# Clocks.net
KiCad netlist of a schematic drawn in Altium Designer
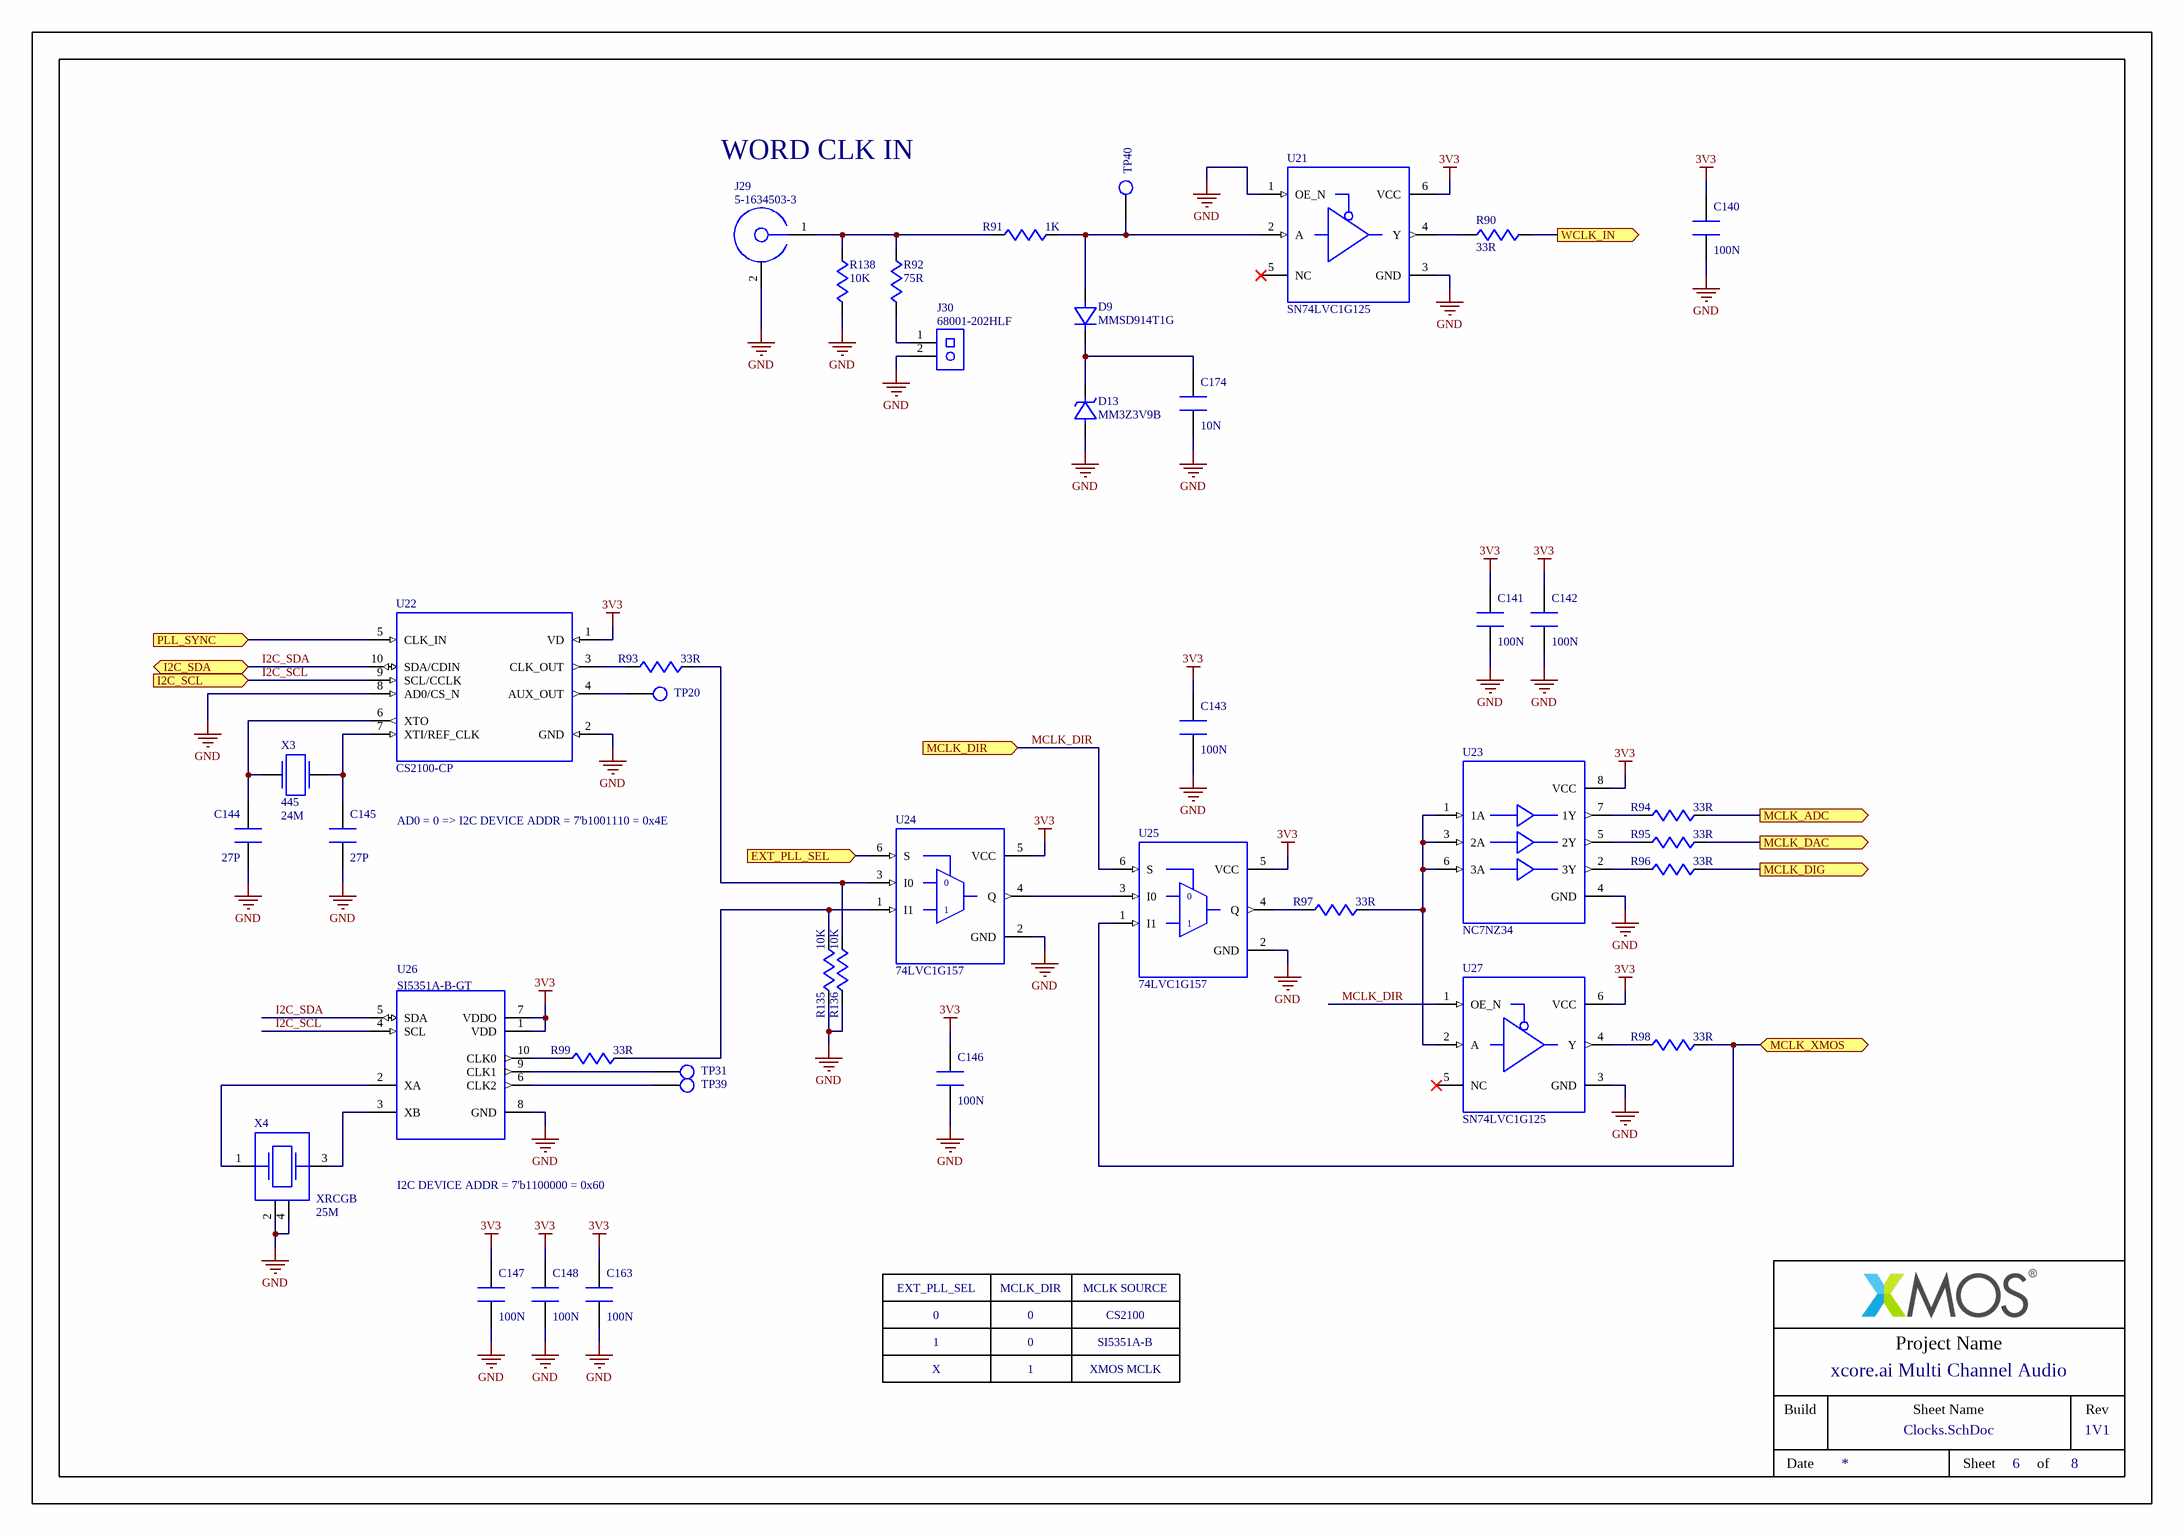
[diagram p0: Clocks.SchDoc]

(export (version "E")
  (design (tool "Eeschema 10.0.6"))
  (components
    (comp (ref "C140")
      (value "100N")
      (footprint "CAPC1005X55N")
      (description "CHIP CAPACITOR, CERAMIC, 100NF, 16V, 10%, X7R, 0402")
      (fields (field (name "PART NUMBER") "STD-06-0048") (field (name "TOLERANCE") "10%"))
      (libsource (lib "JG_StandardLibrary") (part "CAP_NP"))
    )
    (comp (ref "C141")
      (value "100N")
      (footprint "CAPC1005X55N")
      (description "CHIP CAPACITOR, CERAMIC, 100NF, 16V, 10%, X7R, 0402")
      (fields (field (name "PART NUMBER") "STD-06-0048") (field (name "TOLERANCE") "10%"))
      (libsource (lib "JG_StandardLibrary") (part "CAP_NP"))
    )
    (comp (ref "C142")
      (value "100N")
      (footprint "CAPC1005X55N")
      (description "CHIP CAPACITOR, CERAMIC, 100NF, 16V, 10%, X7R, 0402")
      (fields (field (name "PART NUMBER") "STD-06-0048") (field (name "TOLERANCE") "10%"))
      (libsource (lib "JG_StandardLibrary") (part "CAP_NP"))
    )
    (comp (ref "C143")
      (value "100N")
      (footprint "CAPC1005X55N")
      (description "CHIP CAPACITOR, CERAMIC, 100NF, 16V, 10%, X7R, 0402")
      (fields (field (name "PART NUMBER") "STD-06-0048") (field (name "TOLERANCE") "10%"))
      (libsource (lib "JG_StandardLibrary") (part "CAP_NP"))
    )
    (comp (ref "C144")
      (value "27P")
      (footprint "CAPC1005X55N")
      (description "CHIP CAPACITOR, CERAMIC, 27PF, 50V, 5%, NP0, 0402")
      (fields (field (name "PART NUMBER") "STD-06-0018") (field (name "TOLERANCE") "5%"))
      (libsource (lib "JG_StandardLibrary") (part "CAP_NP"))
    )
    (comp (ref "C145")
      (value "27P")
      (footprint "CAPC1005X55N")
      (description "CHIP CAPACITOR, CERAMIC, 27PF, 50V, 5%, NP0, 0402")
      (fields (field (name "PART NUMBER") "STD-06-0018") (field (name "TOLERANCE") "5%"))
      (libsource (lib "JG_StandardLibrary") (part "CAP_NP"))
    )
    (comp (ref "C146")
      (value "100N")
      (footprint "CAPC1005X55N")
      (description "CHIP CAPACITOR, CERAMIC, 100NF, 16V, 10%, X7R, 0402")
      (fields (field (name "PART NUMBER") "STD-06-0048") (field (name "TOLERANCE") "10%"))
      (libsource (lib "JG_StandardLibrary") (part "CAP_NP"))
    )
    (comp (ref "C147")
      (value "100N")
      (footprint "CAPC1005X55N")
      (description "CHIP CAPACITOR, CERAMIC, 100NF, 16V, 10%, X7R, 0402")
      (fields (field (name "PART NUMBER") "STD-06-0048") (field (name "TOLERANCE") "10%"))
      (libsource (lib "JG_StandardLibrary") (part "CAP_NP"))
    )
    (comp (ref "C148")
      (value "100N")
      (footprint "CAPC1005X55N")
      (description "CHIP CAPACITOR, CERAMIC, 100NF, 16V, 10%, X7R, 0402")
      (fields (field (name "PART NUMBER") "STD-06-0048") (field (name "TOLERANCE") "10%"))
      (libsource (lib "JG_StandardLibrary") (part "CAP_NP"))
    )
    (comp (ref "C163")
      (value "100N")
      (footprint "CAPC1005X55N")
      (description "CHIP CAPACITOR, CERAMIC, 100NF, 16V, 10%, X7R, 0402")
      (fields (field (name "PART NUMBER") "STD-06-0048") (field (name "TOLERANCE") "10%"))
      (libsource (lib "JG_StandardLibrary") (part "CAP_NP"))
    )
    (comp (ref "C174")
      (value "10N")
      (footprint "CAPC1005X55N")
      (description "CHIP CAPACITOR, CERAMIC, 10NF, 50V, 10%, X7R, 0402")
      (fields (field (name "PART NUMBER") "STD-06-0042") (field (name "TOLERANCE") "10%"))
      (libsource (lib "JG_StandardLibrary") (part "CAP_NP"))
    )
    (comp (ref "D9")
      (value "MMSD914T1G")
      (footprint "SOD3716X135N")
      (description "Diode, 100V, 0.2A, SOD123")
      (fields (field (name "PART NUMBER") "GEN-16-0055") (field (name "MANUFACTURER") "ON Semiconductor"))
      (libsource (lib "JG_GeneralLibrary") (part "DIODE"))
    )
    (comp (ref "D13")
      (value "MM3Z3V9B")
      (footprint "SODFL2513X100N")
      (description "Zener Diode, 3.9V, 2%, 0.2W, SOD-323F")
      (fields (field (name "PART NUMBER") "GEN-16-0053") (field (name "MANUFACTURER") "ON Semiconductor"))
      (libsource (lib "JG_GeneralLibrary") (part "ZENER"))
    )
    (comp (ref "J29")
      (value "5-1634503-3")
      (footprint "CON_TE_5_1634503")
      (description "BNC Jack, Board Mount, Vertical, 75 ohm, w/Mounting Posts")
      (fields (field (name "PART NUMBER") "GEN-01-0127") (field (name "MANUFACTURER") "TE Connectivity"))
      (libsource (lib "JG_GeneralLibrary") (part "COAX_2_A"))
    )
    (comp (ref "J30")
      (value "68001-202HLF")
      (footprint "HDR_FCI_68001_202")
      (description "Pin Header, Male, Vertical, Through Hole, 2 Way, 1x2, 0.1 Inch Pitch")
      (fields (field (name "PART NUMBER") "GEN-01-0011") (field (name "MANUFACTURER") "FCI"))
      (libsource (lib "JG_GeneralLibrary") (part "PIN_HEADER_1X2"))
    )
    (comp (ref "R90")
      (value "33R")
      (footprint "RESC1608X55N")
      (description "CHIP RESISTOR, 33 OHM, 0.1W, 1%, 0603")
      (fields (field (name "PART NUMBER") "STD-02-0026") (field (name "TOLERANCE") "1%"))
      (libsource (lib "JG_StandardLibrary") (part "RES"))
    )
    (comp (ref "R91")
      (value "1K")
      (footprint "RESC1608X55N")
      (description "CHIP RESISTOR, 1.0K OHM, 0.1W, 1%, 0603")
      (fields (field (name "PART NUMBER") "STD-02-0062") (field (name "TOLERANCE") "1%"))
      (libsource (lib "JG_StandardLibrary") (part "RES"))
    )
    (comp (ref "R92")
      (value "75R")
      (footprint "RESC3116X65N")
      (description "CHIP RESISTOR, 75 OHM, 0.25W, 1%, 1206")
      (fields (field (name "PART NUMBER") "STD-05-0035") (field (name "TOLERANCE") "1%"))
      (libsource (lib "JG_StandardLibrary") (part "RES"))
    )
    (comp (ref "R93")
      (value "33R")
      (footprint "RESC1608X55N")
      (description "CHIP RESISTOR, 33 OHM, 0.1W, 1%, 0603")
      (fields (field (name "PART NUMBER") "STD-02-0026") (field (name "TOLERANCE") "1%"))
      (libsource (lib "JG_StandardLibrary") (part "RES"))
    )
    (comp (ref "R94")
      (value "33R")
      (footprint "RESC1608X55N")
      (description "CHIP RESISTOR, 33 OHM, 0.1W, 1%, 0603")
      (fields (field (name "PART NUMBER") "STD-02-0026") (field (name "TOLERANCE") "1%"))
      (libsource (lib "JG_StandardLibrary") (part "RES"))
    )
    (comp (ref "R95")
      (value "33R")
      (footprint "RESC1608X55N")
      (description "CHIP RESISTOR, 33 OHM, 0.1W, 1%, 0603")
      (fields (field (name "PART NUMBER") "STD-02-0026") (field (name "TOLERANCE") "1%"))
      (libsource (lib "JG_StandardLibrary") (part "RES"))
    )
    (comp (ref "R96")
      (value "33R")
      (footprint "RESC1608X55N")
      (description "CHIP RESISTOR, 33 OHM, 0.1W, 1%, 0603")
      (fields (field (name "PART NUMBER") "STD-02-0026") (field (name "TOLERANCE") "1%"))
      (libsource (lib "JG_StandardLibrary") (part "RES"))
    )
    (comp (ref "R97")
      (value "33R")
      (footprint "RESC1608X55N")
      (description "CHIP RESISTOR, 33 OHM, 0.1W, 1%, 0603")
      (fields (field (name "PART NUMBER") "STD-02-0026") (field (name "TOLERANCE") "1%"))
      (libsource (lib "JG_StandardLibrary") (part "RES"))
    )
    (comp (ref "R98")
      (value "33R")
      (footprint "RESC1608X55N")
      (description "CHIP RESISTOR, 33 OHM, 0.1W, 1%, 0603")
      (fields (field (name "PART NUMBER") "STD-02-0026") (field (name "TOLERANCE") "1%"))
      (libsource (lib "JG_StandardLibrary") (part "RES"))
    )
    (comp (ref "R99")
      (value "33R")
      (footprint "RESC1608X55N")
      (description "CHIP RESISTOR, 33 OHM, 0.1W, 1%, 0603")
      (fields (field (name "PART NUMBER") "STD-02-0026") (field (name "TOLERANCE") "1%"))
      (libsource (lib "JG_StandardLibrary") (part "RES"))
    )
    (comp (ref "R135")
      (value "10K")
      (footprint "RESC1608X55N")
      (description "CHIP RESISTOR, 10K OHM, 0.1W, 1%, 0603")
      (fields (field (name "PART NUMBER") "STD-02-0086") (field (name "TOLERANCE") "1%"))
      (libsource (lib "JG_StandardLibrary") (part "RES"))
    )
    (comp (ref "R136")
      (value "10K")
      (footprint "RESC1608X55N")
      (description "CHIP RESISTOR, 10K OHM, 0.1W, 1%, 0603")
      (fields (field (name "PART NUMBER") "STD-02-0086") (field (name "TOLERANCE") "1%"))
      (libsource (lib "JG_StandardLibrary") (part "RES"))
    )
    (comp (ref "R138")
      (value "10K")
      (footprint "RESC1608X55N")
      (description "CHIP RESISTOR, 10K OHM, 0.1W, 1%, 0603")
      (fields (field (name "PART NUMBER") "STD-02-0086") (field (name "TOLERANCE") "1%"))
      (libsource (lib "JG_StandardLibrary") (part "RES"))
    )
    (comp (ref "TP20")
      (value "TESTPOINT")
      (footprint "TESTPOINT_THRU")
      (description "Testpoint, Through Hole")
      (fields (field (name "PART NUMBER") "GEN-24-0002") (field (name "MANUFACTURER") "NA"))
      (libsource (lib "JG_GeneralLibrary") (part "TESTPOINT"))
    )
    (comp (ref "TP31")
      (value "TESTPOINT")
      (footprint "TESTPOINT_THRU")
      (description "Testpoint, Through Hole")
      (fields (field (name "PART NUMBER") "GEN-24-0002") (field (name "MANUFACTURER") "NA"))
      (libsource (lib "JG_GeneralLibrary") (part "TESTPOINT"))
    )
    (comp (ref "TP39")
      (value "TESTPOINT")
      (footprint "TESTPOINT_THRU")
      (description "Testpoint, Through Hole")
      (fields (field (name "PART NUMBER") "GEN-24-0002") (field (name "MANUFACTURER") "NA"))
      (libsource (lib "JG_GeneralLibrary") (part "TESTPOINT"))
    )
    (comp (ref "TP40")
      (value "TESTPOINT")
      (footprint "TESTPOINT_SMD_1MM")
      (description "Testpoint, SMD, 1mm")
      (fields (field (name "PART NUMBER") "GEN-24-0003") (field (name "MANUFACTURER") "NA"))
      (libsource (lib "JG_GeneralLibrary") (part "TESTPOINT"))
    )
    (comp (ref "U21")
      (value "SN74LVC1G125")
      (footprint "TI_R_PUSON_N6")
      (description "Single Buffer with 3-State Output, LVC Series, SON6")
      (fields (field (name "PART NUMBER") "GEN-11-0049") (field (name "MANUFACTURER") "Texas Instruments"))
      (libsource (lib "JG_GeneralLibrary") (part "SINGLEGATE_125_B"))
    )
    (comp (ref "U22")
      (value "CS2100-CP")
      (footprint "SOP50P490X110-10N")
      (description "Fractional-N Clock Multiplier, I2C/SPI Control, MSOP10")
      (fields (field (name "PART NUMBER") "GEN-07-0007") (field (name "MANUFACTURER") "Cirrus Logic"))
      (libsource (lib "JG_GeneralLibrary") (part "CIRRUS_CS2100_CP"))
    )
    (comp (ref "U23")
      (value "NC7NZ34")
      (footprint "SOP50P310X100-8N")
      (description "Triple Logic Buffer, UHS Series, US8")
      (fields (field (name "PART NUMBER") "GEN-11-0025") (field (name "MANUFACTURER") "Fairchild"))
      (libsource (lib "JG_GeneralLibrary") (part "TRIPLEGATE_34_A"))
    )
    (comp (ref "U24")
      (value "74LVC1G157")
      (footprint "SOT95P280X145-6N")
      (description "Two Input Non-Inverting Multiplexer, LVC Series, TSOP6")
      (fields (field (name "PART NUMBER") "GEN-11-0050") (field (name "MANUFACTURER") "Nexperia"))
      (libsource (lib "JG_GeneralLibrary") (part "SINGLEGATE_157_A"))
    )
    (comp (ref "U25")
      (value "74LVC1G157")
      (footprint "SOT95P280X145-6N")
      (description "Two Input Non-Inverting Multiplexer, LVC Series, TSOP6")
      (fields (field (name "PART NUMBER") "GEN-11-0050") (field (name "MANUFACTURER") "Nexperia"))
      (libsource (lib "JG_GeneralLibrary") (part "SINGLEGATE_157_A"))
    )
    (comp (ref "U26")
      (value "SI5351A-B-GT")
      (footprint "SOP50P490X110-10N")
      (description "Clock Generator, I2C Programmable, XTAL Input, 3 Outputs, MSOP10")
      (fields (field (name "PART NUMBER") "GEN-07-0005") (field (name "MANUFACTURER") "Silicon Labs"))
      (libsource (lib "JG_GeneralLibrary") (part "SI_LABS_SI5351A_MSOP"))
    )
    (comp (ref "U27")
      (value "SN74LVC1G125")
      (footprint "TI_R_PUSON_N6")
      (description "Single Buffer with 3-State Output, LVC Series, SON6")
      (fields (field (name "PART NUMBER") "GEN-11-0049") (field (name "MANUFACTURER") "Texas Instruments"))
      (libsource (lib "JG_GeneralLibrary") (part "SINGLEGATE_125_B"))
    )
    (comp (ref "X3")
      (value "445")
      (footprint "XTAL_CTS_445")
      (description "Crystal, 24MHz, Freq Tol. ±30ppm, Freq Stab. ±30ppm, CL 18pF, Max ESR 40 Ohm, 5x3.2mm SMD")
      (fields
        (field (name "FREQUENCY") "24M")
        (field (name "PART NUMBER") "GEN-15-0041")
        (field (name "MANUFACTURER") "CTS")
      )
      (libsource (lib "JG_GeneralLibrary") (part "CRYSTAL"))
    )
    (comp (ref "X4")
      (value "XRCGB")
      (footprint "OSCCC200X160X70N")
      (description "Crystal, 25MHz, Freq Tol. ±25ppm, Freq Stab. ±40ppm, CL 8pF, Max ESR 80 Ohm, 2.0x1.6mm SMD")
      (fields
        (field (name "FREQUENCY") "25M")
        (field (name "PART NUMBER") "GEN-15-0039")
        (field (name "MANUFACTURER") "Murata")
      )
      (libsource (lib "JG_GeneralLibrary") (part "CRYSTAL_4PIN_A"))
    )
  )
  (nets
    (net (code "1") (name "/EXT_PLL_SEL") (class "Default")
      (node (ref "U24") (pin "6") (pinfunction "S_6") (pintype "input"))
    )
    (net (code "2") (name "/I2C_SCL") (class "Default")
      (node (ref "U22") (pin "9") (pinfunction "SCL/CCLK_9") (pintype "input"))
      (node (ref "U26") (pin "4") (pinfunction "SCL_4") (pintype "input"))
    )
    (net (code "3") (name "/I2C_SDA") (class "Default")
      (node (ref "U22") (pin "10") (pinfunction "SDA/CDIN_10") (pintype "bidirectional"))
      (node (ref "U26") (pin "5") (pinfunction "SDA_5") (pintype "bidirectional"))
    )
    (net (code "4") (name "/MCLK_ADC") (class "Default")
      (node (ref "R94") (pin "2") (pinfunction "2_2") (pintype "passive"))
    )
    (net (code "5") (name "/MCLK_DAC") (class "Default")
      (node (ref "R95") (pin "2") (pinfunction "2_2") (pintype "passive"))
    )
    (net (code "6") (name "/MCLK_DIG") (class "Default")
      (node (ref "R96") (pin "2") (pinfunction "2_2") (pintype "passive"))
    )
    (net (code "7") (name "/MCLK_DIR") (class "Default")
      (node (ref "U25") (pin "6") (pinfunction "S_6") (pintype "input"))
      (node (ref "U27") (pin "1") (pinfunction "OE_N_1") (pintype "input"))
    )
    (net (code "8") (name "/MCLK_XMOS") (class "Default")
      (node (ref "R98") (pin "2") (pinfunction "2_2") (pintype "passive"))
      (node (ref "U25") (pin "1") (pinfunction "I1_1") (pintype "input"))
    )
    (net (code "9") (name "/PLL_SYNC") (class "Default")
      (node (ref "U22") (pin "5") (pinfunction "CLK_IN_5") (pintype "input"))
    )
    (net (code "10") (name "/WCLK_IN") (class "Default")
      (node (ref "R90") (pin "2") (pinfunction "2_2") (pintype "passive"))
    )
    (net (code "11") (name "3V3") (class "Default")
      (node (ref "C140") (pin "1") (pinfunction "1_1") (pintype "passive"))
      (node (ref "C141") (pin "1") (pinfunction "1_1") (pintype "passive"))
      (node (ref "C142") (pin "1") (pinfunction "1_1") (pintype "passive"))
      (node (ref "C143") (pin "1") (pinfunction "1_1") (pintype "passive"))
      (node (ref "C146") (pin "1") (pinfunction "1_1") (pintype "passive"))
      (node (ref "C147") (pin "1") (pinfunction "1_1") (pintype "passive"))
      (node (ref "C148") (pin "1") (pinfunction "1_1") (pintype "passive"))
      (node (ref "C163") (pin "1") (pinfunction "1_1") (pintype "passive"))
      (node (ref "U21") (pin "6") (pinfunction "VCC_6") (pintype "power_in"))
      (node (ref "U22") (pin "1") (pinfunction "VD_1") (pintype "input"))
      (node (ref "U23") (pin "8") (pinfunction "VCC_8") (pintype "power_in"))
      (node (ref "U24") (pin "5") (pinfunction "VCC_5") (pintype "power_in"))
      (node (ref "U25") (pin "5") (pinfunction "VCC_5") (pintype "power_in"))
      (node (ref "U26") (pin "1") (pinfunction "VDD_1") (pintype "power_in"))
      (node (ref "U26") (pin "7") (pinfunction "VDDO_7") (pintype "power_in"))
      (node (ref "U27") (pin "6") (pinfunction "VCC_6") (pintype "power_in"))
    )
    (net (code "12") (name "GND") (class "Default")
      (node (ref "C140") (pin "2") (pinfunction "2_2") (pintype "passive"))
      (node (ref "C141") (pin "2") (pinfunction "2_2") (pintype "passive"))
      (node (ref "C142") (pin "2") (pinfunction "2_2") (pintype "passive"))
      (node (ref "C143") (pin "2") (pinfunction "2_2") (pintype "passive"))
      (node (ref "C144") (pin "2") (pinfunction "2_2") (pintype "passive"))
      (node (ref "C145") (pin "2") (pinfunction "2_2") (pintype "passive"))
      (node (ref "C146") (pin "2") (pinfunction "2_2") (pintype "passive"))
      (node (ref "C147") (pin "2") (pinfunction "2_2") (pintype "passive"))
      (node (ref "C148") (pin "2") (pinfunction "2_2") (pintype "passive"))
      (node (ref "C163") (pin "2") (pinfunction "2_2") (pintype "passive"))
      (node (ref "C174") (pin "2") (pinfunction "2_2") (pintype "passive"))
      (node (ref "D13") (pin "2") (pinfunction "A_2") (pintype "passive"))
      (node (ref "J29") (pin "2") (pinfunction "2_2") (pintype "passive"))
      (node (ref "J30") (pin "2") (pinfunction "2_2") (pintype "passive"))
      (node (ref "R135") (pin "1") (pinfunction "1_1") (pintype "passive"))
      (node (ref "R136") (pin "1") (pinfunction "1_1") (pintype "passive"))
      (node (ref "R138") (pin "1") (pinfunction "1_1") (pintype "passive"))
      (node (ref "U21") (pin "1") (pinfunction "OE_N_1") (pintype "input"))
      (node (ref "U21") (pin "3") (pinfunction "GND_3") (pintype "power_in"))
      (node (ref "U22") (pin "2") (pinfunction "GND_2") (pintype "input"))
      (node (ref "U22") (pin "8") (pinfunction "AD0/CS_N_8") (pintype "input"))
      (node (ref "U23") (pin "4") (pinfunction "GND_4") (pintype "power_in"))
      (node (ref "U24") (pin "2") (pinfunction "GND_2") (pintype "power_in"))
      (node (ref "U25") (pin "2") (pinfunction "GND_2") (pintype "power_in"))
      (node (ref "U26") (pin "8") (pinfunction "GND_8") (pintype "power_in"))
      (node (ref "U27") (pin "3") (pinfunction "GND_3") (pintype "power_in"))
      (node (ref "X4") (pin "2") (pinfunction "CASE_2_2") (pintype "passive"))
      (node (ref "X4") (pin "4") (pinfunction "CASE_4_4") (pintype "passive"))
    )
    (net (code "13") (name "Net-(D9-A)") (class "Default")
      (node (ref "D9") (pin "2") (pinfunction "A_2") (pintype "passive"))
      (node (ref "R91") (pin "2") (pinfunction "2_2") (pintype "passive"))
      (node (ref "TP40") (pin "1") (pinfunction "1_1") (pintype "passive"))
      (node (ref "U21") (pin "2") (pinfunction "A_2") (pintype "input"))
    )
    (net (code "14") (name "Net-(D13-K)") (class "Default")
      (node (ref "C174") (pin "1") (pinfunction "1_1") (pintype "passive"))
      (node (ref "D13") (pin "1") (pinfunction "K_1") (pintype "passive"))
      (node (ref "D9") (pin "1") (pinfunction "K_1") (pintype "passive"))
    )
    (net (code "15") (name "Net-(J29-Pad1)") (class "Default")
      (node (ref "J29") (pin "1") (pinfunction "1_1") (pintype "passive"))
      (node (ref "R138") (pin "2") (pinfunction "2_2") (pintype "passive"))
      (node (ref "R91") (pin "1") (pinfunction "1_1") (pintype "passive"))
      (node (ref "R92") (pin "2") (pinfunction "2_2") (pintype "passive"))
    )
    (net (code "16") (name "Net-(J30-Pad1)") (class "Default")
      (node (ref "J30") (pin "1") (pinfunction "1_1") (pintype "passive"))
      (node (ref "R92") (pin "1") (pinfunction "1_1") (pintype "passive"))
    )
    (net (code "17") (name "Net-(U21-Y)") (class "Default")
      (node (ref "R90") (pin "1") (pinfunction "1_1") (pintype "passive"))
      (node (ref "U21") (pin "4") (pinfunction "Y_4") (pintype "output"))
    )
    (net (code "18") (name "Net-(U22-AUX_OUT)") (class "Default")
      (node (ref "TP20") (pin "1") (pinfunction "1_1") (pintype "passive"))
      (node (ref "U22") (pin "4") (pinfunction "AUX_OUT_4") (pintype "output"))
    )
    (net (code "19") (name "Net-(U22-CLK_OUT)") (class "Default")
      (node (ref "R93") (pin "1") (pinfunction "1_1") (pintype "passive"))
      (node (ref "U22") (pin "3") (pinfunction "CLK_OUT_3") (pintype "output"))
    )
    (net (code "20") (name "Net-(U22-XTI{slash}REF_CLK)") (class "Default")
      (node (ref "C145") (pin "1") (pinfunction "1_1") (pintype "passive"))
      (node (ref "U22") (pin "7") (pinfunction "XTI/REF_CLK_7") (pintype "input"))
      (node (ref "X3") (pin "2") (pinfunction "B_2") (pintype "passive"))
    )
    (net (code "21") (name "Net-(U22-XTO)") (class "Default")
      (node (ref "C144") (pin "1") (pinfunction "1_1") (pintype "passive"))
      (node (ref "U22") (pin "6") (pinfunction "XTO_6") (pintype "output"))
      (node (ref "X3") (pin "1") (pinfunction "A_1") (pintype "passive"))
    )
    (net (code "22") (name "Net-(U23-1A)") (class "Default")
      (node (ref "R97") (pin "2") (pinfunction "2_2") (pintype "passive"))
      (node (ref "U23") (pin "1") (pinfunction "1A_1") (pintype "input"))
      (node (ref "U23") (pin "3") (pinfunction "2A_3") (pintype "input"))
      (node (ref "U23") (pin "6") (pinfunction "3A_6") (pintype "input"))
      (node (ref "U27") (pin "2") (pinfunction "A_2") (pintype "input"))
    )
    (net (code "23") (name "Net-(U23-1Y)") (class "Default")
      (node (ref "R94") (pin "1") (pinfunction "1_1") (pintype "passive"))
      (node (ref "U23") (pin "7") (pinfunction "1Y_7") (pintype "output"))
    )
    (net (code "24") (name "Net-(U23-2Y)") (class "Default")
      (node (ref "R95") (pin "1") (pinfunction "1_1") (pintype "passive"))
      (node (ref "U23") (pin "5") (pinfunction "2Y_5") (pintype "output"))
    )
    (net (code "25") (name "Net-(U23-3Y)") (class "Default")
      (node (ref "R96") (pin "1") (pinfunction "1_1") (pintype "passive"))
      (node (ref "U23") (pin "2") (pinfunction "3Y_2") (pintype "output"))
    )
    (net (code "26") (name "Net-(U24-I0)") (class "Default")
      (node (ref "R136") (pin "2") (pinfunction "2_2") (pintype "passive"))
      (node (ref "R93") (pin "2") (pinfunction "2_2") (pintype "passive"))
      (node (ref "U24") (pin "3") (pinfunction "I0_3") (pintype "input"))
    )
    (net (code "27") (name "Net-(U24-I1)") (class "Default")
      (node (ref "R135") (pin "2") (pinfunction "2_2") (pintype "passive"))
      (node (ref "R99") (pin "2") (pinfunction "2_2") (pintype "passive"))
      (node (ref "U24") (pin "1") (pinfunction "I1_1") (pintype "input"))
    )
    (net (code "28") (name "Net-(U24-Q)") (class "Default")
      (node (ref "U24") (pin "4") (pinfunction "Q_4") (pintype "output"))
      (node (ref "U25") (pin "3") (pinfunction "I0_3") (pintype "input"))
    )
    (net (code "29") (name "Net-(U25-Q)") (class "Default")
      (node (ref "R97") (pin "1") (pinfunction "1_1") (pintype "passive"))
      (node (ref "U25") (pin "4") (pinfunction "Q_4") (pintype "output"))
    )
    (net (code "30") (name "Net-(U26-CLK0)") (class "Default")
      (node (ref "R99") (pin "1") (pinfunction "1_1") (pintype "passive"))
      (node (ref "U26") (pin "10") (pinfunction "CLK0_10") (pintype "output"))
    )
    (net (code "31") (name "Net-(U26-CLK1)") (class "Default")
      (node (ref "TP31") (pin "1") (pinfunction "1_1") (pintype "passive"))
      (node (ref "U26") (pin "9") (pinfunction "CLK1_9") (pintype "output"))
    )
    (net (code "32") (name "Net-(U26-CLK2)") (class "Default")
      (node (ref "TP39") (pin "1") (pinfunction "1_1") (pintype "passive"))
      (node (ref "U26") (pin "6") (pinfunction "CLK2_6") (pintype "output"))
    )
    (net (code "33") (name "Net-(U26-XA)") (class "Default")
      (node (ref "U26") (pin "2") (pinfunction "XA_2") (pintype "passive"))
      (node (ref "X4") (pin "1") (pinfunction "A_1") (pintype "passive"))
    )
    (net (code "34") (name "Net-(U26-XB)") (class "Default")
      (node (ref "U26") (pin "3") (pinfunction "XB_3") (pintype "passive"))
      (node (ref "X4") (pin "3") (pinfunction "B_3") (pintype "passive"))
    )
    (net (code "35") (name "Net-(U27-Y)") (class "Default")
      (node (ref "R98") (pin "1") (pinfunction "1_1") (pintype "passive"))
      (node (ref "U27") (pin "4") (pinfunction "Y_4") (pintype "output"))
    )
    (net (code "36") (name "unconnected-(U21-NC-Pad5)") (class "Default")
      (node (ref "U21") (pin "5") (pinfunction "NC_5") (pintype "passive+no_connect"))
    )
    (net (code "37") (name "unconnected-(U27-NC-Pad5)") (class "Default")
      (node (ref "U27") (pin "5") (pinfunction "NC_5") (pintype "passive+no_connect"))
    )
  )
)
